# badge.net
KiCad netlist of a schematic drawn in EAGLE
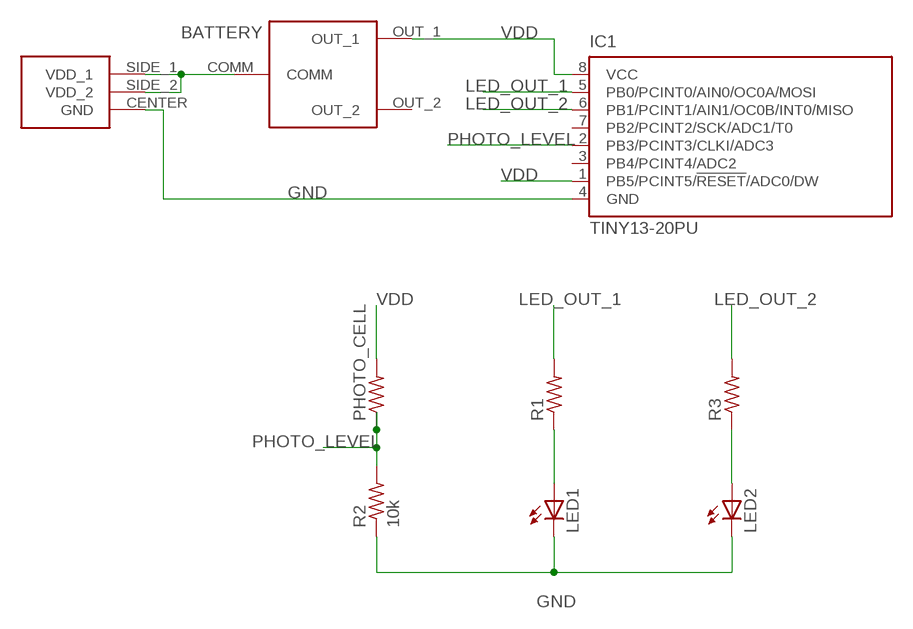
[diagram p0: schematic, sheet 1]

(export (version "E")
  (design (tool "Eeschema 10.0.6"))
  (components
    (comp (ref "IC1")
      (value "TINY13-20PU")
      (footprint "eagle-import:DIL08")
      (fields (field (name "MPN") "ATTINY13-20PU"))
      (libsource (lib "eagle-import") (part "TINY13PU-20"))
    )
    (comp (ref "LED1")
      (value "LED5MM")
      (footprint "eagle-import:LED5MM")
      (libsource (lib "eagle-import") (part "LED5MM"))
    )
    (comp (ref "LED2")
      (value "LED5MM")
      (footprint "eagle-import:LED5MM")
      (libsource (lib "eagle-import") (part "LED5MM"))
    )
    (comp (ref "PHOTO_CELL")
      (value "R-US_0204/7")
      (footprint "eagle-import:0204_7")
      (libsource (lib "eagle-import") (part "R-US_0204/7"))
    )
    (comp (ref "R1")
      (value "R-US_0204/7")
      (footprint "eagle-import:0204_7")
      (libsource (lib "eagle-import") (part "R-US_0204/7"))
    )
    (comp (ref "R2")
      (value "10k")
      (footprint "eagle-import:0204_7")
      (libsource (lib "eagle-import") (part "R-US_0204/7"))
    )
    (comp (ref "R3")
      (value "R-US_0204/7")
      (footprint "eagle-import:0204_7")
      (libsource (lib "eagle-import") (part "R-US_0204/7"))
    )
    (comp (ref "U$1")
      (value "COIN_CELL_SPARKFUN")
      (footprint "eagle-import:COIN_CELL_SPARKFUN")
      (libsource (lib "eagle-import") (part "COIN_CELL_SPARKFUN"))
    )
    (comp (ref "U$2")
      (value "SPST_SPARKFUN")
      (footprint "eagle-import:SPDT_SPARKFUN")
      (libsource (lib "eagle-import") (part "SPST_SPARKFUN"))
    )
  )
  (nets
    (net (code "1") (name "/BATTERY") (class "Default")
      (node (ref "U$1") (pin "SIDE_1") (pinfunction "VDD_1_SIDE_1") (pintype "bidirectional"))
      (node (ref "U$1") (pin "SIDE_2") (pinfunction "VDD_2_SIDE_2") (pintype "bidirectional"))
      (node (ref "U$2") (pin "COMM") (pinfunction "COMM_COMM") (pintype "bidirectional"))
    )
    (net (code "2") (name "/GND") (class "Default")
      (node (ref "IC1") (pin "4") (pinfunction "GND_4") (pintype "power_in"))
      (node (ref "LED1") (pin "K") (pinfunction "C_K") (pintype "passive"))
      (node (ref "LED2") (pin "K") (pinfunction "C_K") (pintype "passive"))
      (node (ref "R2") (pin "1") (pinfunction "1_1") (pintype "passive"))
      (node (ref "U$1") (pin "CENTER") (pinfunction "GND_CENTER") (pintype "bidirectional"))
    )
    (net (code "3") (name "/LED_OUT_1") (class "Default")
      (node (ref "IC1") (pin "5") (pinfunction "PB0/PCINT0/AIN0/OC0A/MOSI_5") (pintype "bidirectional"))
      (node (ref "R1") (pin "2") (pinfunction "2_2") (pintype "passive"))
    )
    (net (code "4") (name "/LED_OUT_2") (class "Default")
      (node (ref "IC1") (pin "6") (pinfunction "PB1/PCINT1/AIN1/OC0B/INT0/MISO_6") (pintype "bidirectional"))
      (node (ref "R3") (pin "2") (pinfunction "2_2") (pintype "passive"))
    )
    (net (code "5") (name "/PHOTO_LEVEL") (class "Default")
      (node (ref "IC1") (pin "2") (pinfunction "PB3/PCINT3/CLKI/ADC3_2") (pintype "bidirectional"))
      (node (ref "PHOTO_CELL") (pin "1") (pinfunction "1_1") (pintype "passive"))
      (node (ref "R2") (pin "2") (pinfunction "2_2") (pintype "passive"))
    )
    (net (code "6") (name "/VDD") (class "Default")
      (node (ref "IC1") (pin "1") (pinfunction "PB5/PCINT5/~{RESET}/ADC0/DW_1") (pintype "bidirectional"))
      (node (ref "IC1") (pin "8") (pinfunction "VCC_8") (pintype "power_in"))
      (node (ref "PHOTO_CELL") (pin "2") (pinfunction "2_2") (pintype "passive"))
      (node (ref "U$2") (pin "OUT_1") (pinfunction "OUT_1_OUT_1") (pintype "bidirectional"))
    )
    (net (code "7") (name "Net-(LED1-PadA)") (class "Default")
      (node (ref "LED1") (pin "A") (pinfunction "A_A") (pintype "passive"))
      (node (ref "R1") (pin "1") (pinfunction "1_1") (pintype "passive"))
    )
    (net (code "8") (name "Net-(LED2-PadA)") (class "Default")
      (node (ref "LED2") (pin "A") (pinfunction "A_A") (pintype "passive"))
      (node (ref "R3") (pin "1") (pinfunction "1_1") (pintype "passive"))
    )
    (net (code "9") (name "unconnected-(IC1-PB2{slash}PCINT2{slash}SCK{slash}ADC1{slash}T0-Pad7)") (class "Default")
      (node (ref "IC1") (pin "7") (pinfunction "PB2/PCINT2/SCK/ADC1/T0_7") (pintype "bidirectional"))
    )
    (net (code "10") (name "unconnected-(IC1-PB4{slash}PCINT4{slash}ADC2-Pad3)") (class "Default")
      (node (ref "IC1") (pin "3") (pinfunction "PB4/PCINT4/ADC2_3") (pintype "bidirectional"))
    )
    (net (code "11") (name "unconnected-(U$2-PadOUT_2)") (class "Default")
      (node (ref "U$2") (pin "OUT_2") (pinfunction "OUT_2_OUT_2") (pintype "bidirectional"))
    )
  )
)
